# RF_Sheet.net
KiCad netlist of a schematic drawn in Altium Designer
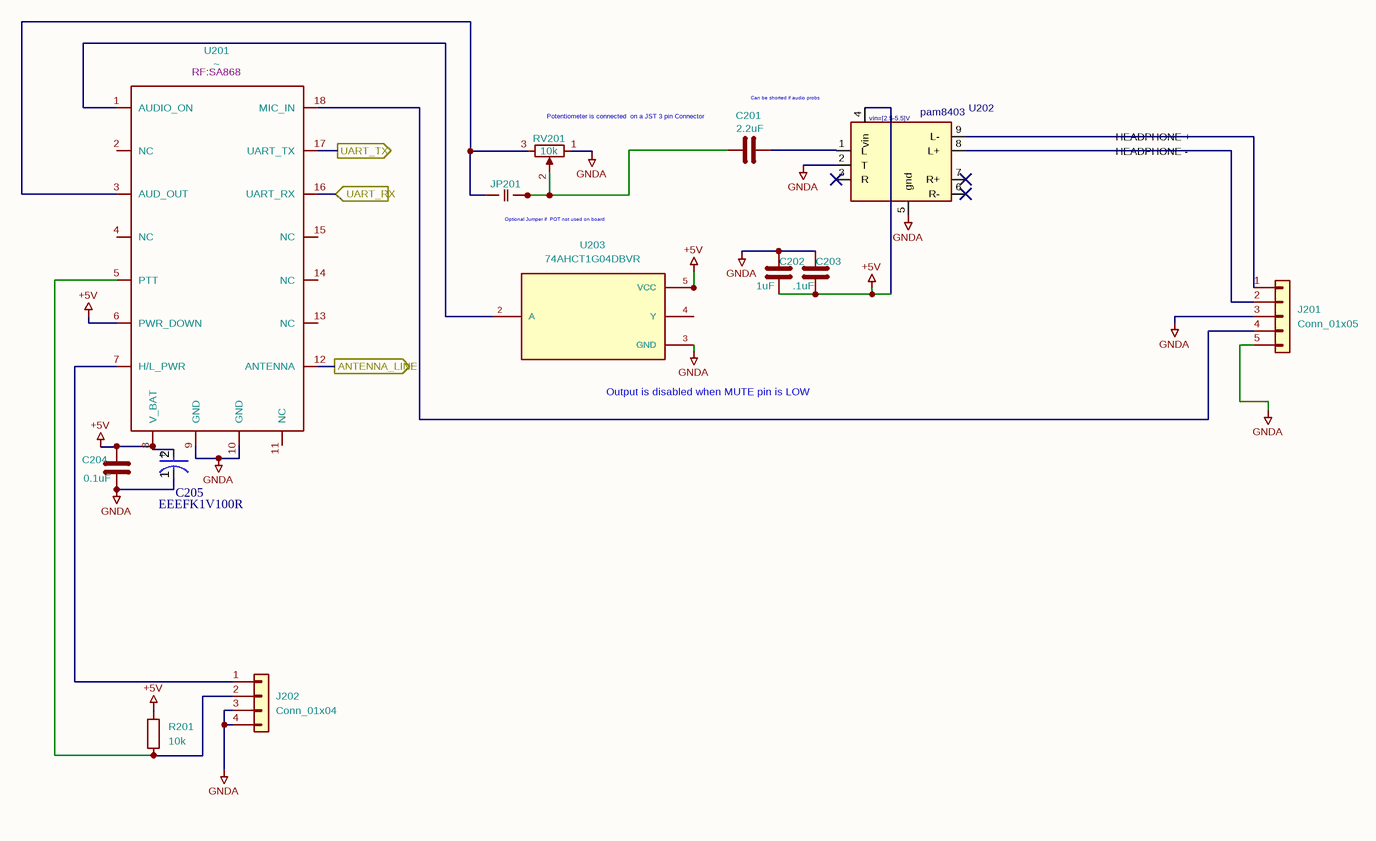
[diagram p0: RF Sheet.SchDoc]

(export (version "E")
  (design (tool "Eeschema 10.0.6"))
  (components
    (comp (ref "C201")
      (value "2.2uF")
      (footprint "C_0603_1608Metric_Pad1.08x0.95mm_HandSolder")
      (libsource (lib "Device") (part "C"))
    )
    (comp (ref "C202")
      (value "1uF")
      (footprint "C_0603_1608Metric_Pad1.08x0.95mm_HandSolder")
      (libsource (lib "Device") (part "C"))
    )
    (comp (ref "C203")
      (value ".1uF")
      (footprint "C_0603_1608Metric_Pad1.08x0.95mm_HandSolder")
      (libsource (lib "Device") (part "C"))
    )
    (comp (ref "C204")
      (value "0.1uF")
      (footprint "C_0603_1608Metric_Pad1.08x0.95mm_HandSolder")
      (libsource (lib "Device") (part "C"))
    )
    (comp (ref "C205")
      (value "EEEFK1V100R")
      (footprint "FP-FKC-MFG")
      (description "CAP ALUM 10UF 20% 35V SMD")
      (fields (field (name "TOLERANCE") "20%") (field (name "VOLTAGE") "35V"))
      (libsource (lib "Altium Content Vault") (part "203bc49f2ac43e59fd269a8c329ed05"))
    )
    (comp (ref "J201")
      (value "Conn_01x05")
      (footprint "JST_XH_B05B-XH-A_05x2.50mm_Straight")
      (libsource (lib "Connector_Generic") (part "Conn_01x05"))
    )
    (comp (ref "J202")
      (value "Conn_01x04")
      (footprint "JST_XH_B4B-XH-A_1x04_P2.50mm_Vertical")
      (libsource (lib "Connector_Generic") (part "Conn_01x04"))
    )
    (comp (ref "JP201")
      (value "SolderJumper_2_Open")
      (footprint "R_1206_3216Metric_Pad1.30x1.75mm_HandSolder")
      (libsource (lib "Jumper") (part "SolderJumper_2_Open"))
    )
    (comp (ref "R201")
      (value "10k")
      (footprint "R_1206_3216Metric_Pad1.30x1.75mm_HandSolder")
      (libsource (lib "Device") (part "R"))
    )
    (comp (ref "RV201")
      (value "10k")
      (footprint "JST_XH_B3B-XH-A_1x03_P2.50mm_Vertical")
      (libsource (lib "Device") (part "R_Potentiometer"))
    )
    (comp (ref "U201") (value "~") (footprint "RF:SA868") (libsource (lib "RF") (part "SA868")))
    (comp (ref "U202") (value "pam8403") (footprint "pam8403") (libsource (lib "pam8403") (part "pam8403")))
    (comp (ref "U203")
      (value "74AHCT1G04DBVR")
      (footprint "SOT-23-5")
      (fields (field (name "MF") "Texas Instruments") (field (name "MP") "SN74AHCT1G04DBVR"))
      (libsource (lib "74xGxx") (part "74AHCT1G04DBVR"))
    )
  )
  (nets
    (net (code "1") (name "+5V") (class "Default")
      (node (ref "C202") (pin "2") (pinfunction "2_2") (pintype "passive"))
      (node (ref "C203") (pin "2") (pinfunction "2_2") (pintype "passive"))
      (node (ref "C204") (pin "1") (pinfunction "1_1") (pintype "passive"))
      (node (ref "C205") (pin "2") (pinfunction "A_2") (pintype "passive"))
      (node (ref "R201") (pin "1") (pinfunction "1_1") (pintype "passive"))
      (node (ref "U201") (pin "6") (pinfunction "PWR_DOWN_6") (pintype "passive"))
      (node (ref "U201") (pin "8") (pinfunction "V_BAT_8") (pintype "passive"))
      (node (ref "U202") (pin "4") (pinfunction "vin_4") (pintype "passive"))
      (node (ref "U203") (pin "5") (pinfunction "VCC_5") (pintype "passive"))
    )
    (net (code "2") (name "/ANTENNA_LINE") (class "Default")
      (node (ref "U201") (pin "12") (pinfunction "ANTENNA_12") (pintype "passive"))
    )
    (net (code "5") (name "/UART_RX") (class "Default")
      (node (ref "U201") (pin "16") (pinfunction "UART_RX_16") (pintype "passive"))
    )
    (net (code "6") (name "/UART_TX") (class "Default")
      (node (ref "U201") (pin "17") (pinfunction "UART_TX_17") (pintype "passive"))
    )
    (net (code "7") (name "GNDA") (class "Default")
      (node (ref "C202") (pin "1") (pinfunction "1_1") (pintype "passive"))
      (node (ref "C203") (pin "1") (pinfunction "1_1") (pintype "passive"))
      (node (ref "C204") (pin "2") (pinfunction "2_2") (pintype "passive"))
      (node (ref "C205") (pin "1") (pinfunction "C_1") (pintype "passive"))
      (node (ref "J201") (pin "3") (pinfunction "Pin_3_3") (pintype "passive"))
      (node (ref "J201") (pin "5") (pinfunction "Pin_5_5") (pintype "passive"))
      (node (ref "J202") (pin "3") (pinfunction "Pin_3_3") (pintype "passive"))
      (node (ref "J202") (pin "4") (pinfunction "Pin_4_4") (pintype "passive"))
      (node (ref "RV201") (pin "1") (pinfunction "1_1") (pintype "passive"))
      (node (ref "U201") (pin "10") (pinfunction "GND_10") (pintype "passive"))
      (node (ref "U201") (pin "9") (pinfunction "GND_9") (pintype "passive"))
      (node (ref "U202") (pin "2") (pinfunction "T_2") (pintype "passive"))
      (node (ref "U202") (pin "5") (pinfunction "gnd_5") (pintype "passive"))
      (node (ref "U203") (pin "3") (pinfunction "GND_3") (pintype "passive"))
    )
    (net (code "8") (name "Net-(J201-Pin_1)") (class "Default")
      (node (ref "J201") (pin "1") (pinfunction "Pin_1_1") (pintype "passive"))
      (node (ref "U202") (pin "9") (pinfunction "L-_9") (pintype "passive"))
    )
    (net (code "9") (name "Net-(J201-Pin_2)") (class "Default")
      (node (ref "J201") (pin "2") (pinfunction "Pin_2_2") (pintype "passive"))
      (node (ref "U202") (pin "8") (pinfunction "L+_8") (pintype "passive"))
    )
    (net (code "10") (name "Net-(J201-Pin_4)") (class "Default")
      (node (ref "J201") (pin "4") (pinfunction "Pin_4_4") (pintype "passive"))
      (node (ref "U201") (pin "18") (pinfunction "MIC_IN_18") (pintype "passive"))
    )
    (net (code "11") (name "Net-(J202-Pin_1)") (class "Default")
      (node (ref "J202") (pin "1") (pinfunction "Pin_1_1") (pintype "passive"))
      (node (ref "U201") (pin "7") (pinfunction "H/L_PWR_7") (pintype "passive"))
    )
    (net (code "12") (name "Net-(J202-Pin_2)") (class "Default")
      (node (ref "J202") (pin "2") (pinfunction "Pin_2_2") (pintype "passive"))
      (node (ref "R201") (pin "2") (pinfunction "2_2") (pintype "passive"))
      (node (ref "U201") (pin "5") (pinfunction "PTT_5") (pintype "passive"))
    )
    (net (code "13") (name "Net-(JP201-A)") (class "Default")
      (node (ref "JP201") (pin "1") (pinfunction "A_1") (pintype "passive"))
      (node (ref "RV201") (pin "3") (pinfunction "3_3") (pintype "passive"))
      (node (ref "U201") (pin "3") (pinfunction "AUD_OUT_3") (pintype "passive"))
    )
    (net (code "14") (name "Net-(JP201-B)") (class "Default")
      (node (ref "C201") (pin "1") (pinfunction "1_1") (pintype "passive"))
      (node (ref "JP201") (pin "2") (pinfunction "B_2") (pintype "passive"))
      (node (ref "RV201") (pin "2") (pinfunction "2_2") (pintype "passive"))
    )
    (net (code "15") (name "Net-(U201-AUDIO_ON)") (class "Default")
      (node (ref "U201") (pin "1") (pinfunction "AUDIO_ON_1") (pintype "passive"))
      (node (ref "U203") (pin "2") (pinfunction "A_2") (pintype "passive"))
    )
    (net (code "16") (name "Net-(U202-L)") (class "Default")
      (node (ref "C201") (pin "2") (pinfunction "2_2") (pintype "passive"))
      (node (ref "U202") (pin "1") (pinfunction "L_1") (pintype "passive"))
    )
    (net (code "17") (name "unconnected-(U201-NC-Pad2)") (class "Default")
      (node (ref "U201") (pin "2") (pinfunction "NC_2") (pintype "passive"))
    )
    (net (code "18") (name "unconnected-(U201-NC-Pad4)") (class "Default")
      (node (ref "U201") (pin "4") (pinfunction "NC_4") (pintype "passive"))
    )
    (net (code "19") (name "unconnected-(U201-NC-Pad11)") (class "Default")
      (node (ref "U201") (pin "11") (pinfunction "NC_11") (pintype "passive"))
    )
    (net (code "20") (name "unconnected-(U201-NC-Pad13)") (class "Default")
      (node (ref "U201") (pin "13") (pinfunction "NC_13") (pintype "passive"))
    )
    (net (code "21") (name "unconnected-(U201-NC-Pad14)") (class "Default")
      (node (ref "U201") (pin "14") (pinfunction "NC_14") (pintype "passive"))
    )
    (net (code "22") (name "unconnected-(U201-NC-Pad15)") (class "Default")
      (node (ref "U201") (pin "15") (pinfunction "NC_15") (pintype "passive"))
    )
    (net (code "23") (name "unconnected-(U202-R+-Pad7)") (class "Default")
      (node (ref "U202") (pin "7") (pinfunction "R+_7") (pintype "passive+no_connect"))
    )
    (net (code "24") (name "unconnected-(U202-R--Pad6)") (class "Default")
      (node (ref "U202") (pin "6") (pinfunction "R-_6") (pintype "passive+no_connect"))
    )
    (net (code "25") (name "unconnected-(U202-R-Pad3)") (class "Default")
      (node (ref "U202") (pin "3") (pinfunction "R_3") (pintype "passive+no_connect"))
    )
    (net (code "26") (name "unconnected-(U203-Y-Pad4)") (class "Default")
      (node (ref "U203") (pin "4") (pinfunction "Y_4") (pintype "passive"))
    )
  )
)
